# CubeNode.net
KiCad netlist of a schematic drawn in Altium Designer
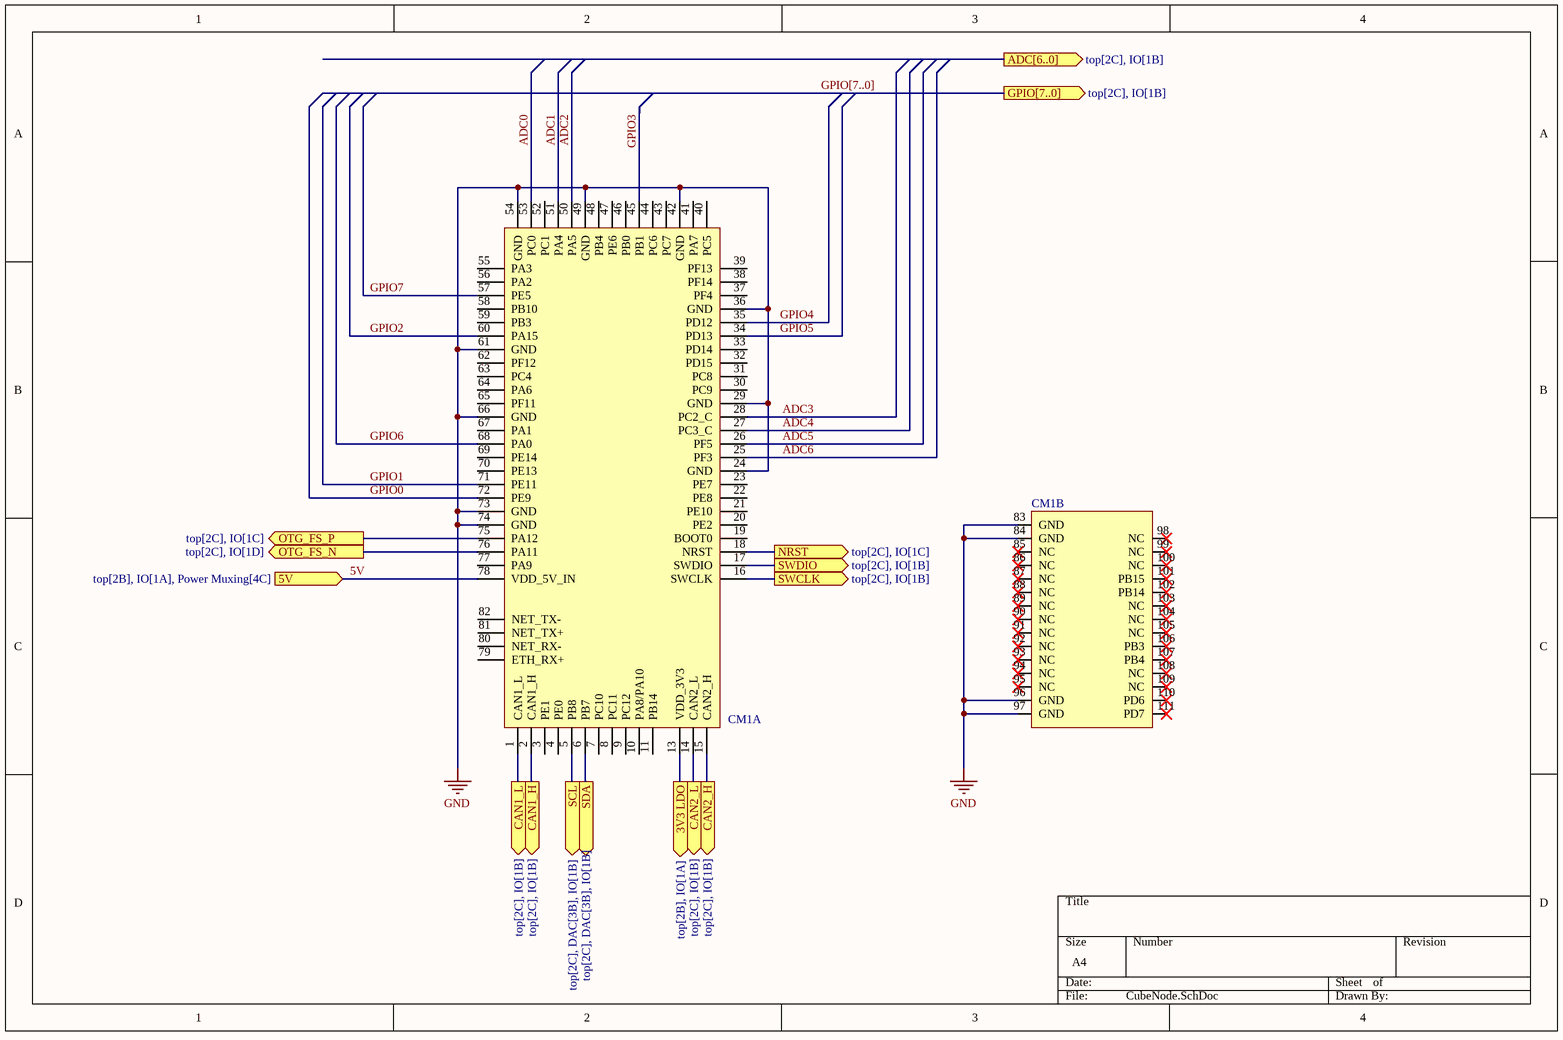
[diagram p0: CubeNode.SchDoc]

(export (version "E")
  (design (tool "Eeschema 10.0.6"))
  (components
    (comp (ref "CM1")
      (value "CUBENODE_FOOTPRINT")
      (footprint "CubeNode Footprint:CubeNode")
      (libsource (lib "") (part "CubeNode Footprint_1"))
    )
  )
  (nets
    (net (code "1") (name "/3V3 LDO") (class "Default")
      (node (ref "CM1") (pin "13") (pinfunction "VDD_3V3_13") (pintype "passive"))
    )
    (net (code "2") (name "/5V") (class "Default")
      (node (ref "CM1") (pin "78") (pinfunction "VDD_5V_IN_78") (pintype "passive"))
    )
    (net (code "7") (name "/ADC4") (class "Default")
      (node (ref "CM1") (pin "27") (pinfunction "PC3_C_27") (pintype "passive"))
    )
    (net (code "8") (name "/ADC5") (class "Default")
      (node (ref "CM1") (pin "26") (pinfunction "PF5_26") (pintype "passive"))
    )
    (net (code "9") (name "/ADC6") (class "Default")
      (node (ref "CM1") (pin "25") (pinfunction "PF3_25") (pintype "passive"))
    )
    (net (code "11") (name "/CAN1_H") (class "Default")
      (node (ref "CM1") (pin "2") (pinfunction "CAN1_H_2") (pintype "passive"))
    )
    (net (code "12") (name "/CAN1_L") (class "Default")
      (node (ref "CM1") (pin "1") (pinfunction "CAN1_L_1") (pintype "passive"))
    )
    (net (code "13") (name "/CAN2_H") (class "Default")
      (node (ref "CM1") (pin "15") (pinfunction "CAN2_H_15") (pintype "passive"))
    )
    (net (code "14") (name "/CAN2_L") (class "Default")
      (node (ref "CM1") (pin "14") (pinfunction "CAN2_L_14") (pintype "passive"))
    )
    (net (code "15") (name "/GPIO0") (class "Default")
      (node (ref "CM1") (pin "72") (pinfunction "PE9_72") (pintype "passive"))
    )
    (net (code "16") (name "/GPIO1") (class "Default")
      (node (ref "CM1") (pin "71") (pinfunction "PE11_71") (pintype "passive"))
    )
    (net (code "17") (name "/GPIO2") (class "Default")
      (node (ref "CM1") (pin "60") (pinfunction "PA15_60") (pintype "passive"))
    )
    (net (code "18") (name "/GPIO3") (class "Default")
      (node (ref "CM1") (pin "45") (pinfunction "PB1_45") (pintype "passive"))
    )
    (net (code "19") (name "/GPIO4") (class "Default")
      (node (ref "CM1") (pin "35") (pinfunction "PD12_35") (pintype "passive"))
    )
    (net (code "20") (name "/GPIO5") (class "Default")
      (node (ref "CM1") (pin "34") (pinfunction "PD13_34") (pintype "passive"))
    )
    (net (code "21") (name "/GPIO6") (class "Default")
      (node (ref "CM1") (pin "68") (pinfunction "PA0_68") (pintype "passive"))
    )
    (net (code "22") (name "/GPIO7") (class "Default")
      (node (ref "CM1") (pin "57") (pinfunction "PE5_57") (pintype "passive"))
    )
    (net (code "24") (name "/NRST") (class "Default")
      (node (ref "CM1") (pin "18") (pinfunction "NRST_18") (pintype "passive"))
    )
    (net (code "25") (name "/OTG_FS_N") (class "Default")
      (node (ref "CM1") (pin "76") (pinfunction "PA11_76") (pintype "passive"))
    )
    (net (code "26") (name "/OTG_FS_P") (class "Default")
      (node (ref "CM1") (pin "75") (pinfunction "PA12_75") (pintype "passive"))
    )
    (net (code "27") (name "/SCL") (class "Default")
      (node (ref "CM1") (pin "5") (pinfunction "PB8_5") (pintype "passive"))
    )
    (net (code "28") (name "/SDA") (class "Default")
      (node (ref "CM1") (pin "6") (pinfunction "PB7_6") (pintype "passive"))
    )
    (net (code "29") (name "/SWCLK") (class "Default")
      (node (ref "CM1") (pin "16") (pinfunction "SWCLK_16") (pintype "passive"))
    )
    (net (code "30") (name "/SWDIO") (class "Default")
      (node (ref "CM1") (pin "17") (pinfunction "SWDIO_17") (pintype "passive"))
    )
    (net (code "31") (name "GND") (class "Default")
      (node (ref "CM1") (pin "24") (pinfunction "GND_24") (pintype "passive"))
      (node (ref "CM1") (pin "29") (pinfunction "GND_29") (pintype "passive"))
      (node (ref "CM1") (pin "36") (pinfunction "GND_36") (pintype "passive"))
      (node (ref "CM1") (pin "42") (pinfunction "GND_42") (pintype "passive"))
      (node (ref "CM1") (pin "49") (pinfunction "GND_49") (pintype "passive"))
      (node (ref "CM1") (pin "54") (pinfunction "GND_54") (pintype "passive"))
      (node (ref "CM1") (pin "61") (pinfunction "GND_61") (pintype "passive"))
      (node (ref "CM1") (pin "66") (pinfunction "GND_66") (pintype "passive"))
      (node (ref "CM1") (pin "73") (pinfunction "GND_73") (pintype "passive"))
      (node (ref "CM1") (pin "74") (pinfunction "GND_74") (pintype "passive"))
      (node (ref "CM1") (pin "83") (pinfunction "GND_83") (pintype "passive"))
      (node (ref "CM1") (pin "84") (pinfunction "GND_84") (pintype "passive"))
      (node (ref "CM1") (pin "96") (pinfunction "GND_96") (pintype "passive"))
      (node (ref "CM1") (pin "97") (pinfunction "GND_97") (pintype "passive"))
    )
    (net (code "32") (name "unconnected-(CM1A-BOOT0-Pad19)") (class "Default")
      (node (ref "CM1") (pin "19") (pinfunction "BOOT0_19") (pintype "passive"))
    )
    (net (code "33") (name "unconnected-(CM1A-ETH_RX+-Pad79)") (class "Default")
      (node (ref "CM1") (pin "79") (pinfunction "ETH_RX+_79") (pintype "passive"))
    )
    (net (code "34") (name "unconnected-(CM1A-NET_RX--Pad80)") (class "Default")
      (node (ref "CM1") (pin "80") (pinfunction "NET_RX-_80") (pintype "passive"))
    )
    (net (code "35") (name "unconnected-(CM1A-NET_TX+-Pad81)") (class "Default")
      (node (ref "CM1") (pin "81") (pinfunction "NET_TX+_81") (pintype "passive"))
    )
    (net (code "36") (name "unconnected-(CM1A-NET_TX--Pad82)") (class "Default")
      (node (ref "CM1") (pin "82") (pinfunction "NET_TX-_82") (pintype "passive"))
    )
    (net (code "37") (name "unconnected-(CM1A-PA1-Pad67)") (class "Default")
      (node (ref "CM1") (pin "67") (pinfunction "PA1_67") (pintype "passive"))
    )
    (net (code "38") (name "unconnected-(CM1A-PA2-Pad56)") (class "Default")
      (node (ref "CM1") (pin "56") (pinfunction "PA2_56") (pintype "passive"))
    )
    (net (code "39") (name "unconnected-(CM1A-PA3-Pad55)") (class "Default")
      (node (ref "CM1") (pin "55") (pinfunction "PA3_55") (pintype "passive"))
    )
    (net (code "40") (name "unconnected-(CM1A-PA4-Pad51)") (class "Default")
      (node (ref "CM1") (pin "51") (pinfunction "PA4_51") (pintype "passive"))
    )
    (net (code "41") (name "unconnected-(CM1A-PA5-Pad50)") (class "Default")
      (node (ref "CM1") (pin "50") (pinfunction "PA5_50") (pintype "passive"))
    )
    (net (code "42") (name "unconnected-(CM1A-PA6-Pad64)") (class "Default")
      (node (ref "CM1") (pin "64") (pinfunction "PA6_64") (pintype "passive"))
    )
    (net (code "43") (name "unconnected-(CM1A-PA7-Pad41)") (class "Default")
      (node (ref "CM1") (pin "41") (pinfunction "PA7_41") (pintype "passive"))
    )
    (net (code "44") (name "unconnected-(CM1A-PA8{slash}PA10-Pad10)") (class "Default")
      (node (ref "CM1") (pin "10") (pinfunction "PA8/PA10_10") (pintype "passive"))
    )
    (net (code "45") (name "unconnected-(CM1A-PA9-Pad77)") (class "Default")
      (node (ref "CM1") (pin "77") (pinfunction "PA9_77") (pintype "passive"))
    )
    (net (code "46") (name "unconnected-(CM1A-PB0-Pad46)") (class "Default")
      (node (ref "CM1") (pin "46") (pinfunction "PB0_46") (pintype "passive"))
    )
    (net (code "47") (name "unconnected-(CM1A-PB3-Pad59)") (class "Default")
      (node (ref "CM1") (pin "59") (pinfunction "PB3_59") (pintype "passive"))
    )
    (net (code "48") (name "unconnected-(CM1A-PB4-Pad48)") (class "Default")
      (node (ref "CM1") (pin "48") (pinfunction "PB4_48") (pintype "passive"))
    )
    (net (code "49") (name "unconnected-(CM1A-PB10-Pad58)") (class "Default")
      (node (ref "CM1") (pin "58") (pinfunction "PB10_58") (pintype "passive"))
    )
    (net (code "50") (name "unconnected-(CM1A-PB14-Pad11)") (class "Default")
      (node (ref "CM1") (pin "11") (pinfunction "PB14_11") (pintype "passive"))
    )
    (net (code "51") (name "unconnected-(CM1A-PC0-Pad53)") (class "Default")
      (node (ref "CM1") (pin "53") (pinfunction "PC0_53") (pintype "passive"))
    )
    (net (code "52") (name "unconnected-(CM1A-PC1-Pad52)") (class "Default")
      (node (ref "CM1") (pin "52") (pinfunction "PC1_52") (pintype "passive"))
    )
    (net (code "53") (name "unconnected-(CM1A-PC2_C-Pad28)") (class "Default")
      (node (ref "CM1") (pin "28") (pinfunction "PC2_C_28") (pintype "passive"))
    )
    (net (code "54") (name "unconnected-(CM1A-PC4-Pad63)") (class "Default")
      (node (ref "CM1") (pin "63") (pinfunction "PC4_63") (pintype "passive"))
    )
    (net (code "55") (name "unconnected-(CM1A-PC5-Pad40)") (class "Default")
      (node (ref "CM1") (pin "40") (pinfunction "PC5_40") (pintype "passive"))
    )
    (net (code "56") (name "unconnected-(CM1A-PC6-Pad44)") (class "Default")
      (node (ref "CM1") (pin "44") (pinfunction "PC6_44") (pintype "passive"))
    )
    (net (code "57") (name "unconnected-(CM1A-PC7-Pad43)") (class "Default")
      (node (ref "CM1") (pin "43") (pinfunction "PC7_43") (pintype "passive"))
    )
    (net (code "58") (name "unconnected-(CM1A-PC8-Pad31)") (class "Default")
      (node (ref "CM1") (pin "31") (pinfunction "PC8_31") (pintype "passive"))
    )
    (net (code "59") (name "unconnected-(CM1A-PC9-Pad30)") (class "Default")
      (node (ref "CM1") (pin "30") (pinfunction "PC9_30") (pintype "passive"))
    )
    (net (code "60") (name "unconnected-(CM1A-PC10-Pad7)") (class "Default")
      (node (ref "CM1") (pin "7") (pinfunction "PC10_7") (pintype "passive"))
    )
    (net (code "61") (name "unconnected-(CM1A-PC11-Pad8)") (class "Default")
      (node (ref "CM1") (pin "8") (pinfunction "PC11_8") (pintype "passive"))
    )
    (net (code "62") (name "unconnected-(CM1A-PC12-Pad9)") (class "Default")
      (node (ref "CM1") (pin "9") (pinfunction "PC12_9") (pintype "passive"))
    )
    (net (code "63") (name "unconnected-(CM1A-PD14-Pad33)") (class "Default")
      (node (ref "CM1") (pin "33") (pinfunction "PD14_33") (pintype "passive"))
    )
    (net (code "64") (name "unconnected-(CM1A-PD15-Pad32)") (class "Default")
      (node (ref "CM1") (pin "32") (pinfunction "PD15_32") (pintype "passive"))
    )
    (net (code "65") (name "unconnected-(CM1A-PE0-Pad4)") (class "Default")
      (node (ref "CM1") (pin "4") (pinfunction "PE0_4") (pintype "passive"))
    )
    (net (code "66") (name "unconnected-(CM1A-PE1-Pad3)") (class "Default")
      (node (ref "CM1") (pin "3") (pinfunction "PE1_3") (pintype "passive"))
    )
    (net (code "67") (name "unconnected-(CM1A-PE2-Pad20)") (class "Default")
      (node (ref "CM1") (pin "20") (pinfunction "PE2_20") (pintype "passive"))
    )
    (net (code "68") (name "unconnected-(CM1A-PE6-Pad47)") (class "Default")
      (node (ref "CM1") (pin "47") (pinfunction "PE6_47") (pintype "passive"))
    )
    (net (code "69") (name "unconnected-(CM1A-PE7-Pad23)") (class "Default")
      (node (ref "CM1") (pin "23") (pinfunction "PE7_23") (pintype "passive"))
    )
    (net (code "70") (name "unconnected-(CM1A-PE8-Pad22)") (class "Default")
      (node (ref "CM1") (pin "22") (pinfunction "PE8_22") (pintype "passive"))
    )
    (net (code "71") (name "unconnected-(CM1A-PE10-Pad21)") (class "Default")
      (node (ref "CM1") (pin "21") (pinfunction "PE10_21") (pintype "passive"))
    )
    (net (code "72") (name "unconnected-(CM1A-PE13-Pad70)") (class "Default")
      (node (ref "CM1") (pin "70") (pinfunction "PE13_70") (pintype "passive"))
    )
    (net (code "73") (name "unconnected-(CM1A-PE14-Pad69)") (class "Default")
      (node (ref "CM1") (pin "69") (pinfunction "PE14_69") (pintype "passive"))
    )
    (net (code "74") (name "unconnected-(CM1A-PF4-Pad37)") (class "Default")
      (node (ref "CM1") (pin "37") (pinfunction "PF4_37") (pintype "passive"))
    )
    (net (code "75") (name "unconnected-(CM1A-PF11-Pad65)") (class "Default")
      (node (ref "CM1") (pin "65") (pinfunction "PF11_65") (pintype "passive"))
    )
    (net (code "76") (name "unconnected-(CM1A-PF12-Pad62)") (class "Default")
      (node (ref "CM1") (pin "62") (pinfunction "PF12_62") (pintype "passive"))
    )
    (net (code "77") (name "unconnected-(CM1A-PF13-Pad39)") (class "Default")
      (node (ref "CM1") (pin "39") (pinfunction "PF13_39") (pintype "passive"))
    )
    (net (code "78") (name "unconnected-(CM1A-PF14-Pad38)") (class "Default")
      (node (ref "CM1") (pin "38") (pinfunction "PF14_38") (pintype "passive"))
    )
    (net (code "79") (name "unconnected-(CM1B-NC-Pad85)") (class "Default")
      (node (ref "CM1") (pin "85") (pinfunction "NC_85") (pintype "passive+no_connect"))
    )
    (net (code "80") (name "unconnected-(CM1B-NC-Pad86)") (class "Default")
      (node (ref "CM1") (pin "86") (pinfunction "NC_86") (pintype "passive+no_connect"))
    )
    (net (code "81") (name "unconnected-(CM1B-NC-Pad87)") (class "Default")
      (node (ref "CM1") (pin "87") (pinfunction "NC_87") (pintype "passive+no_connect"))
    )
    (net (code "82") (name "unconnected-(CM1B-NC-Pad88)") (class "Default")
      (node (ref "CM1") (pin "88") (pinfunction "NC_88") (pintype "passive+no_connect"))
    )
    (net (code "83") (name "unconnected-(CM1B-NC-Pad89)") (class "Default")
      (node (ref "CM1") (pin "89") (pinfunction "NC_89") (pintype "passive+no_connect"))
    )
    (net (code "84") (name "unconnected-(CM1B-NC-Pad90)") (class "Default")
      (node (ref "CM1") (pin "90") (pinfunction "NC_90") (pintype "passive+no_connect"))
    )
    (net (code "85") (name "unconnected-(CM1B-NC-Pad91)") (class "Default")
      (node (ref "CM1") (pin "91") (pinfunction "NC_91") (pintype "passive+no_connect"))
    )
    (net (code "86") (name "unconnected-(CM1B-NC-Pad92)") (class "Default")
      (node (ref "CM1") (pin "92") (pinfunction "NC_92") (pintype "passive+no_connect"))
    )
    (net (code "87") (name "unconnected-(CM1B-NC-Pad93)") (class "Default")
      (node (ref "CM1") (pin "93") (pinfunction "NC_93") (pintype "passive+no_connect"))
    )
    (net (code "88") (name "unconnected-(CM1B-NC-Pad94)") (class "Default")
      (node (ref "CM1") (pin "94") (pinfunction "NC_94") (pintype "passive+no_connect"))
    )
    (net (code "89") (name "unconnected-(CM1B-NC-Pad95)") (class "Default")
      (node (ref "CM1") (pin "95") (pinfunction "NC_95") (pintype "passive+no_connect"))
    )
    (net (code "90") (name "unconnected-(CM1B-NC-Pad98)") (class "Default")
      (node (ref "CM1") (pin "98") (pinfunction "NC_98") (pintype "passive+no_connect"))
    )
    (net (code "91") (name "unconnected-(CM1B-NC-Pad99)") (class "Default")
      (node (ref "CM1") (pin "99") (pinfunction "NC_99") (pintype "passive+no_connect"))
    )
    (net (code "92") (name "unconnected-(CM1B-NC-Pad100)") (class "Default")
      (node (ref "CM1") (pin "100") (pinfunction "NC_100") (pintype "passive+no_connect"))
    )
    (net (code "93") (name "unconnected-(CM1B-NC-Pad103)") (class "Default")
      (node (ref "CM1") (pin "103") (pinfunction "NC_103") (pintype "passive+no_connect"))
    )
    (net (code "94") (name "unconnected-(CM1B-NC-Pad104)") (class "Default")
      (node (ref "CM1") (pin "104") (pinfunction "NC_104") (pintype "passive+no_connect"))
    )
    (net (code "95") (name "unconnected-(CM1B-NC-Pad105)") (class "Default")
      (node (ref "CM1") (pin "105") (pinfunction "NC_105") (pintype "passive+no_connect"))
    )
    (net (code "96") (name "unconnected-(CM1B-NC-Pad108)") (class "Default")
      (node (ref "CM1") (pin "108") (pinfunction "NC_108") (pintype "passive+no_connect"))
    )
    (net (code "97") (name "unconnected-(CM1B-NC-Pad109)") (class "Default")
      (node (ref "CM1") (pin "109") (pinfunction "NC_109") (pintype "passive+no_connect"))
    )
    (net (code "98") (name "unconnected-(CM1B-PB3-Pad106)") (class "Default")
      (node (ref "CM1") (pin "106") (pinfunction "PB3_106") (pintype "passive+no_connect"))
    )
    (net (code "99") (name "unconnected-(CM1B-PB4-Pad107)") (class "Default")
      (node (ref "CM1") (pin "107") (pinfunction "PB4_107") (pintype "passive+no_connect"))
    )
    (net (code "100") (name "unconnected-(CM1B-PB14-Pad102)") (class "Default")
      (node (ref "CM1") (pin "102") (pinfunction "PB14_102") (pintype "passive+no_connect"))
    )
    (net (code "101") (name "unconnected-(CM1B-PB15-Pad101)") (class "Default")
      (node (ref "CM1") (pin "101") (pinfunction "PB15_101") (pintype "passive+no_connect"))
    )
    (net (code "102") (name "unconnected-(CM1B-PD6-Pad110)") (class "Default")
      (node (ref "CM1") (pin "110") (pinfunction "PD6_110") (pintype "passive+no_connect"))
    )
    (net (code "103") (name "unconnected-(CM1B-PD7-Pad111)") (class "Default")
      (node (ref "CM1") (pin "111") (pinfunction "PD7_111") (pintype "passive+no_connect"))
    )
  )
)
